# eight_slider_breakout.net
KiCad netlist of a schematic drawn in EAGLE
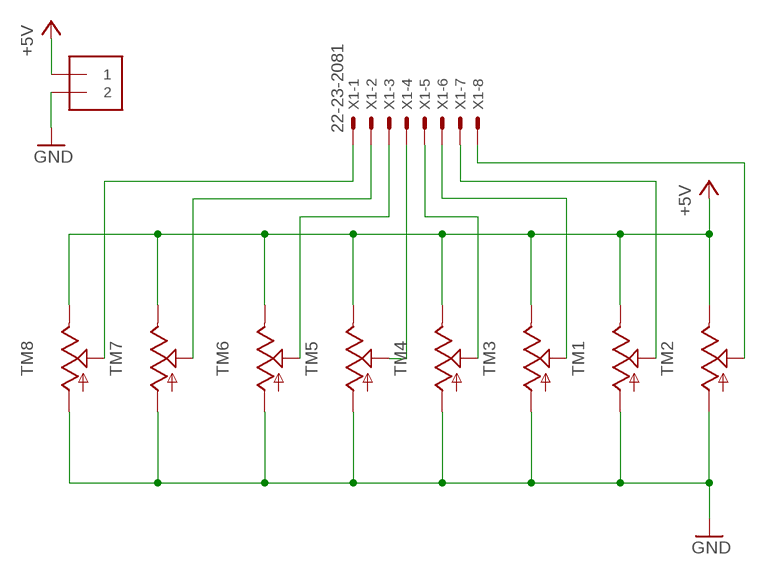
[diagram p0: schematic, sheet 1]

(export (version "E")
  (design (tool "Eeschema 10.0.6"))
  (components
    (comp (ref "J1")
      (value "1X2-3.5MM")
      (footprint "eagle-import:1X2-3.5MM")
      (libsource (lib "eagle-import") (part "1X2-3.5MM"))
    )
    (comp (ref "TM1")
      (value "TRIMSLIDE60")
      (footprint "eagle-import:SLIDEPOT-60")
      (libsource (lib "eagle-import") (part "TRIMSLIDE60"))
    )
    (comp (ref "TM2")
      (value "TRIMSLIDE60")
      (footprint "eagle-import:SLIDEPOT-60")
      (libsource (lib "eagle-import") (part "TRIMSLIDE60"))
    )
    (comp (ref "TM3")
      (value "TRIMSLIDE60")
      (footprint "eagle-import:SLIDEPOT-60")
      (libsource (lib "eagle-import") (part "TRIMSLIDE60"))
    )
    (comp (ref "TM4")
      (value "TRIMSLIDE60")
      (footprint "eagle-import:SLIDEPOT-60")
      (libsource (lib "eagle-import") (part "TRIMSLIDE60"))
    )
    (comp (ref "TM5")
      (value "TRIMSLIDE60")
      (footprint "eagle-import:SLIDEPOT-60")
      (libsource (lib "eagle-import") (part "TRIMSLIDE60"))
    )
    (comp (ref "TM6")
      (value "TRIMSLIDE60")
      (footprint "eagle-import:SLIDEPOT-60")
      (libsource (lib "eagle-import") (part "TRIMSLIDE60"))
    )
    (comp (ref "TM7")
      (value "TRIMSLIDE60")
      (footprint "eagle-import:SLIDEPOT-60")
      (libsource (lib "eagle-import") (part "TRIMSLIDE60"))
    )
    (comp (ref "TM8")
      (value "TRIMSLIDE60")
      (footprint "eagle-import:SLIDEPOT-60")
      (libsource (lib "eagle-import") (part "TRIMSLIDE60"))
    )
    (comp (ref "X1")
      (value "22-23-2081")
      (footprint "eagle-import:22-23-2081")
      (fields (field (name "MF") "MOLEX"))
      (libsource (lib "eagle-import") (part "22-23-2081"))
    )
  )
  (nets
    (net (code "1") (name "+5V") (class "Default")
      (node (ref "J1") (pin "1") (pinfunction "1_1") (pintype "passive"))
      (node (ref "TM1") (pin "B") (pinfunction "B_B") (pintype "passive"))
      (node (ref "TM2") (pin "B") (pinfunction "B_B") (pintype "passive"))
      (node (ref "TM3") (pin "B") (pinfunction "B_B") (pintype "passive"))
      (node (ref "TM4") (pin "B") (pinfunction "B_B") (pintype "passive"))
      (node (ref "TM5") (pin "B") (pinfunction "B_B") (pintype "passive"))
      (node (ref "TM6") (pin "B") (pinfunction "B_B") (pintype "passive"))
      (node (ref "TM7") (pin "B") (pinfunction "B_B") (pintype "passive"))
      (node (ref "TM8") (pin "B") (pinfunction "B_B") (pintype "passive"))
    )
    (net (code "2") (name "GND") (class "Default")
      (node (ref "J1") (pin "2") (pinfunction "2_2") (pintype "passive"))
      (node (ref "TM1") (pin "A") (pinfunction "A_A") (pintype "passive"))
      (node (ref "TM2") (pin "A") (pinfunction "A_A") (pintype "passive"))
      (node (ref "TM3") (pin "A") (pinfunction "A_A") (pintype "passive"))
      (node (ref "TM4") (pin "A") (pinfunction "A_A") (pintype "passive"))
      (node (ref "TM5") (pin "A") (pinfunction "A_A") (pintype "passive"))
      (node (ref "TM6") (pin "A") (pinfunction "A_A") (pintype "passive"))
      (node (ref "TM7") (pin "A") (pinfunction "A_A") (pintype "passive"))
      (node (ref "TM8") (pin "A") (pinfunction "A_A") (pintype "passive"))
    )
    (net (code "3") (name "Net-(X1A-S)") (class "Default")
      (node (ref "TM8") (pin "WIPER") (pinfunction "WIPER_WIPER") (pintype "passive"))
      (node (ref "X1") (pin "1") (pinfunction "S_1") (pintype "passive"))
    )
    (net (code "4") (name "Net-(X1B-S)") (class "Default")
      (node (ref "TM7") (pin "WIPER") (pinfunction "WIPER_WIPER") (pintype "passive"))
      (node (ref "X1") (pin "2") (pinfunction "S_2") (pintype "passive"))
    )
    (net (code "5") (name "Net-(X1C-S)") (class "Default")
      (node (ref "TM6") (pin "WIPER") (pinfunction "WIPER_WIPER") (pintype "passive"))
      (node (ref "X1") (pin "3") (pinfunction "S_3") (pintype "passive"))
    )
    (net (code "6") (name "Net-(X1D-S)") (class "Default")
      (node (ref "TM5") (pin "WIPER") (pinfunction "WIPER_WIPER") (pintype "passive"))
      (node (ref "X1") (pin "4") (pinfunction "S_4") (pintype "passive"))
    )
    (net (code "7") (name "Net-(X1E-S)") (class "Default")
      (node (ref "TM4") (pin "WIPER") (pinfunction "WIPER_WIPER") (pintype "passive"))
      (node (ref "X1") (pin "5") (pinfunction "S_5") (pintype "passive"))
    )
    (net (code "8") (name "Net-(X1F-S)") (class "Default")
      (node (ref "TM3") (pin "WIPER") (pinfunction "WIPER_WIPER") (pintype "passive"))
      (node (ref "X1") (pin "6") (pinfunction "S_6") (pintype "passive"))
    )
    (net (code "9") (name "Net-(X1G-S)") (class "Default")
      (node (ref "TM1") (pin "WIPER") (pinfunction "WIPER_WIPER") (pintype "passive"))
      (node (ref "X1") (pin "7") (pinfunction "S_7") (pintype "passive"))
    )
    (net (code "10") (name "Net-(X1H-S)") (class "Default")
      (node (ref "TM2") (pin "WIPER") (pinfunction "WIPER_WIPER") (pintype "passive"))
      (node (ref "X1") (pin "8") (pinfunction "S_8") (pintype "passive"))
    )
  )
)
